# Neural_Interface.net
KiCad netlist of a schematic drawn in Altium Designer
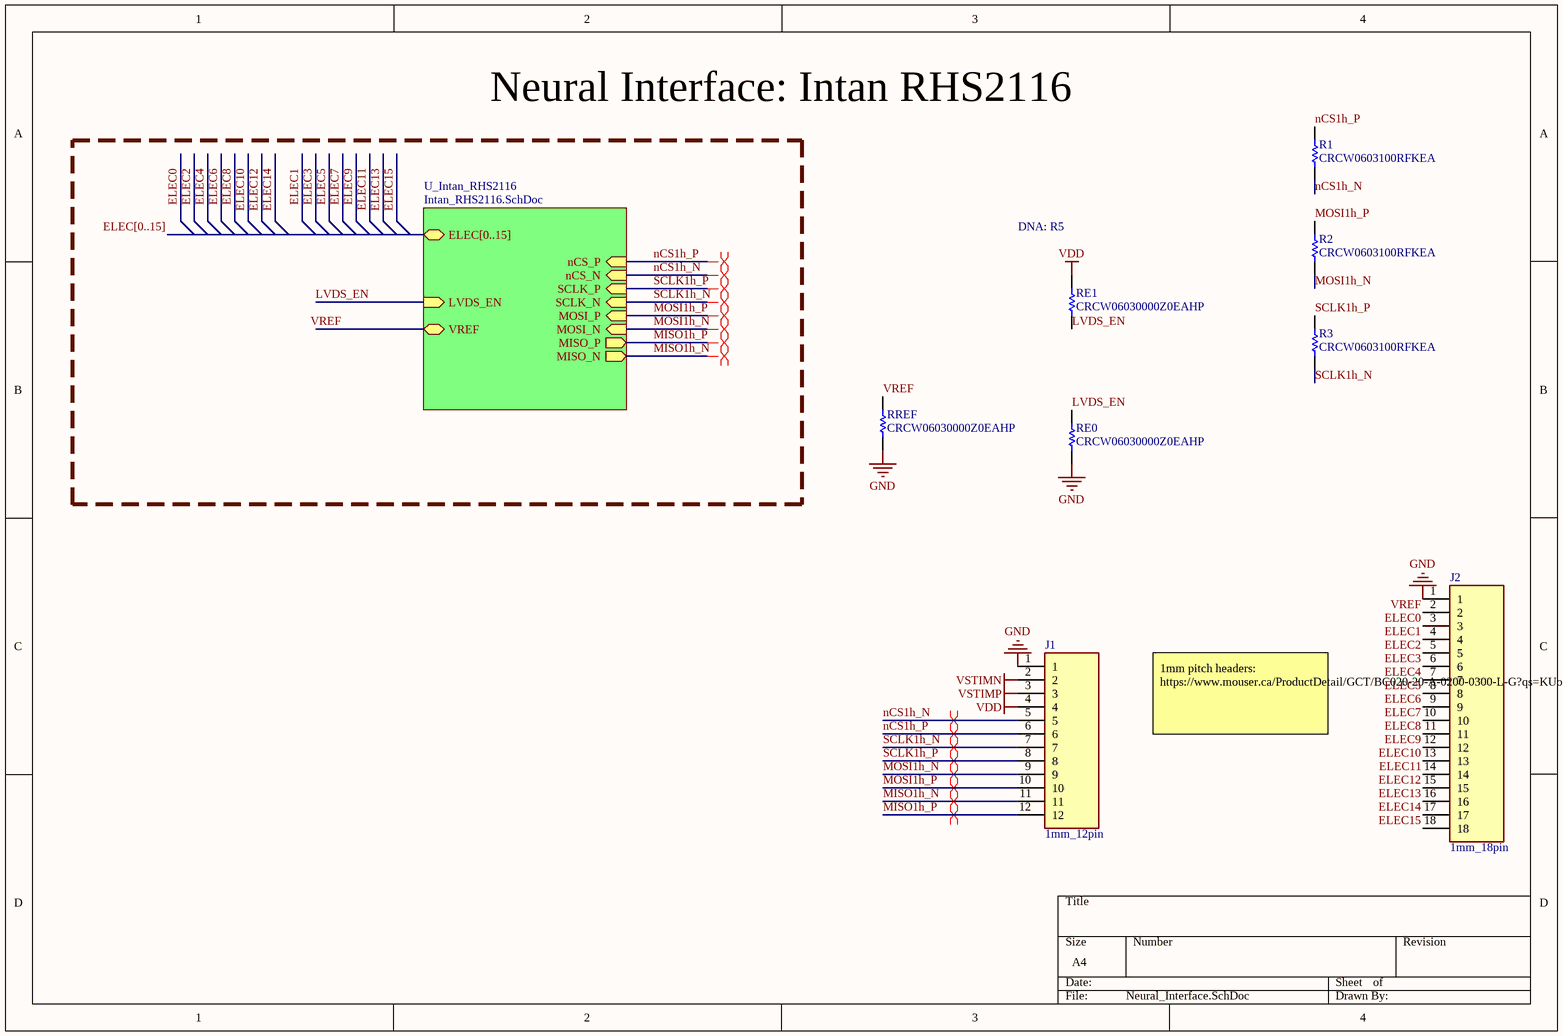
[diagram p0: Neural_Interface.SchDoc]

(export (version "E")
  (design (tool "Eeschema 10.0.6"))
  (components
    (comp (ref "J1")
      (value "1mm_12pin")
      (footprint "1mm_12pin")
      (libsource (lib "Neural_Interface") (part "1mm_12pin"))
    )
    (comp (ref "J2")
      (value "1mm_18pin")
      (footprint "1mm_18pin")
      (libsource (lib "Neural_Interface") (part "1mm_18pin"))
    )
    (comp (ref "R1")
      (value "CRCW0603100RFKEA")
      (footprint "RESC1609X50X30ML8T20")
      (description "Chip Resistor, 100 Ohm, +/- 1%, 100 mW,-55 to 155 degC, 0603 (1608 Metric), RoHS, Tape and Ree")
      (fields (field (name "MANUFACTURER") "Vishay Semiconductor"))
      (libsource (lib "Altium Content Vault") (part "RES-2"))
    )
    (comp (ref "R2")
      (value "CRCW0603100RFKEA")
      (footprint "RESC1609X50X30ML8T20")
      (description "Chip Resistor, 100 Ohm, +/- 1%, 100 mW,-55 to 155 degC, 0603 (1608 Metric), RoHS, Tape and Ree")
      (fields (field (name "MANUFACTURER") "Vishay Semiconductor"))
      (libsource (lib "Altium Content Vault") (part "RES-2"))
    )
    (comp (ref "R3")
      (value "CRCW0603100RFKEA")
      (footprint "RESC1609X50X30ML8T20")
      (description "Chip Resistor, 100 Ohm, +/- 1%, 100 mW,-55 to 155 degC, 0603 (1608 Metric), RoHS, Tape and Ree")
      (fields (field (name "MANUFACTURER") "Vishay Semiconductor"))
      (libsource (lib "Altium Content Vault") (part "RES-2"))
    )
    (comp (ref "RE0")
      (value "CRCW06030000Z0EAHP")
      (footprint "RESC1609X55X30NL10T20")
      (fields (field (name "MANUFACTURER") "Vishay Dale"))
      (libsource (lib "Altium Content Vault") (part "RES"))
    )
    (comp (ref "RE1")
      (value "CRCW06030000Z0EAHP")
      (footprint "RESC1609X55X30NL10T20")
      (fields (field (name "MANUFACTURER") "Vishay Dale"))
      (libsource (lib "Altium Content Vault") (part "RES"))
    )
    (comp (ref "RREF")
      (value "CRCW06030000Z0EAHP")
      (footprint "RESC1609X55X30NL10T20")
      (fields (field (name "MANUFACTURER") "Vishay Dale"))
      (libsource (lib "Altium Content Vault") (part "RES"))
    )
  )
  (nets
    (net (code "1") (name "/ELEC0") (class "Default")
      (node (ref "J2") (pin "3") (pinfunction "3_3") (pintype "passive"))
    )
    (net (code "2") (name "/ELEC1") (class "Default")
      (node (ref "J2") (pin "4") (pinfunction "4_4") (pintype "passive"))
    )
    (net (code "3") (name "/ELEC2") (class "Default")
      (node (ref "J2") (pin "5") (pinfunction "5_5") (pintype "passive"))
    )
    (net (code "4") (name "/ELEC3") (class "Default")
      (node (ref "J2") (pin "6") (pinfunction "6_6") (pintype "passive"))
    )
    (net (code "5") (name "/ELEC4") (class "Default")
      (node (ref "J2") (pin "7") (pinfunction "7_7") (pintype "passive"))
    )
    (net (code "6") (name "/ELEC5") (class "Default")
      (node (ref "J2") (pin "8") (pinfunction "8_8") (pintype "passive"))
    )
    (net (code "7") (name "/ELEC6") (class "Default")
      (node (ref "J2") (pin "9") (pinfunction "9_9") (pintype "passive"))
    )
    (net (code "8") (name "/ELEC7") (class "Default")
      (node (ref "J2") (pin "10") (pinfunction "10_10") (pintype "passive"))
    )
    (net (code "9") (name "/ELEC8") (class "Default")
      (node (ref "J2") (pin "11") (pinfunction "11_11") (pintype "passive"))
    )
    (net (code "10") (name "/ELEC9") (class "Default")
      (node (ref "J2") (pin "12") (pinfunction "12_12") (pintype "passive"))
    )
    (net (code "11") (name "/ELEC10") (class "Default")
      (node (ref "J2") (pin "13") (pinfunction "13_13") (pintype "passive"))
    )
    (net (code "12") (name "/ELEC11") (class "Default")
      (node (ref "J2") (pin "14") (pinfunction "14_14") (pintype "passive"))
    )
    (net (code "13") (name "/ELEC12") (class "Default")
      (node (ref "J2") (pin "15") (pinfunction "15_15") (pintype "passive"))
    )
    (net (code "14") (name "/ELEC13") (class "Default")
      (node (ref "J2") (pin "16") (pinfunction "16_16") (pintype "passive"))
    )
    (net (code "15") (name "/ELEC14") (class "Default")
      (node (ref "J2") (pin "17") (pinfunction "17_17") (pintype "passive"))
    )
    (net (code "16") (name "/ELEC15") (class "Default")
      (node (ref "J2") (pin "18") (pinfunction "18_18") (pintype "passive"))
    )
    (net (code "18") (name "/LVDS_EN") (class "Default")
      (node (ref "RE0") (pin "2") (pinfunction "2_2") (pintype "passive"))
      (node (ref "RE1") (pin "1") (pinfunction "1_1") (pintype "passive"))
    )
    (net (code "19") (name "/MISO1h_N") (class "Default")
      (node (ref "J1") (pin "11") (pinfunction "11_11") (pintype "passive"))
    )
    (net (code "20") (name "/MISO1h_P") (class "Default")
      (node (ref "J1") (pin "12") (pinfunction "12_12") (pintype "passive"))
    )
    (net (code "21") (name "/MOSI1h_N") (class "Default")
      (node (ref "J1") (pin "9") (pinfunction "9_9") (pintype "passive"))
      (node (ref "R2") (pin "1") (pinfunction "1_1") (pintype "passive"))
    )
    (net (code "22") (name "/MOSI1h_P") (class "Default")
      (node (ref "J1") (pin "10") (pinfunction "10_10") (pintype "passive"))
      (node (ref "R2") (pin "2") (pinfunction "2_2") (pintype "passive"))
    )
    (net (code "23") (name "/SCLK1h_N") (class "Default")
      (node (ref "J1") (pin "7") (pinfunction "7_7") (pintype "passive"))
      (node (ref "R3") (pin "1") (pinfunction "1_1") (pintype "passive"))
    )
    (net (code "24") (name "/SCLK1h_P") (class "Default")
      (node (ref "J1") (pin "8") (pinfunction "8_8") (pintype "passive"))
      (node (ref "R3") (pin "2") (pinfunction "2_2") (pintype "passive"))
    )
    (net (code "25") (name "/VREF") (class "Default")
      (node (ref "J2") (pin "2") (pinfunction "2_2") (pintype "passive"))
      (node (ref "RREF") (pin "2") (pinfunction "2_2") (pintype "passive"))
    )
    (net (code "26") (name "/nCS1h_N") (class "Default")
      (node (ref "J1") (pin "5") (pinfunction "5_5") (pintype "passive"))
      (node (ref "R1") (pin "1") (pinfunction "1_1") (pintype "passive"))
    )
    (net (code "27") (name "/nCS1h_P") (class "Default")
      (node (ref "J1") (pin "6") (pinfunction "6_6") (pintype "passive"))
      (node (ref "R1") (pin "2") (pinfunction "2_2") (pintype "passive"))
    )
    (net (code "28") (name "GND") (class "Default")
      (node (ref "J1") (pin "1") (pinfunction "1_1") (pintype "passive"))
      (node (ref "J2") (pin "1") (pinfunction "1_1") (pintype "passive"))
      (node (ref "RE0") (pin "1") (pinfunction "1_1") (pintype "passive"))
      (node (ref "RREF") (pin "1") (pinfunction "1_1") (pintype "passive"))
    )
    (net (code "29") (name "VDD") (class "Default")
      (node (ref "J1") (pin "4") (pinfunction "4_4") (pintype "passive"))
      (node (ref "RE1") (pin "2") (pinfunction "2_2") (pintype "passive"))
    )
    (net (code "30") (name "VSTIMN") (class "Default")
      (node (ref "J1") (pin "2") (pinfunction "2_2") (pintype "passive"))
    )
    (net (code "31") (name "VSTIMP") (class "Default")
      (node (ref "J1") (pin "3") (pinfunction "3_3") (pintype "passive"))
    )
  )
)
